# Fri3d_2024_Exp0_00.net
KiCad netlist of a schematic drawn in Altium Designer
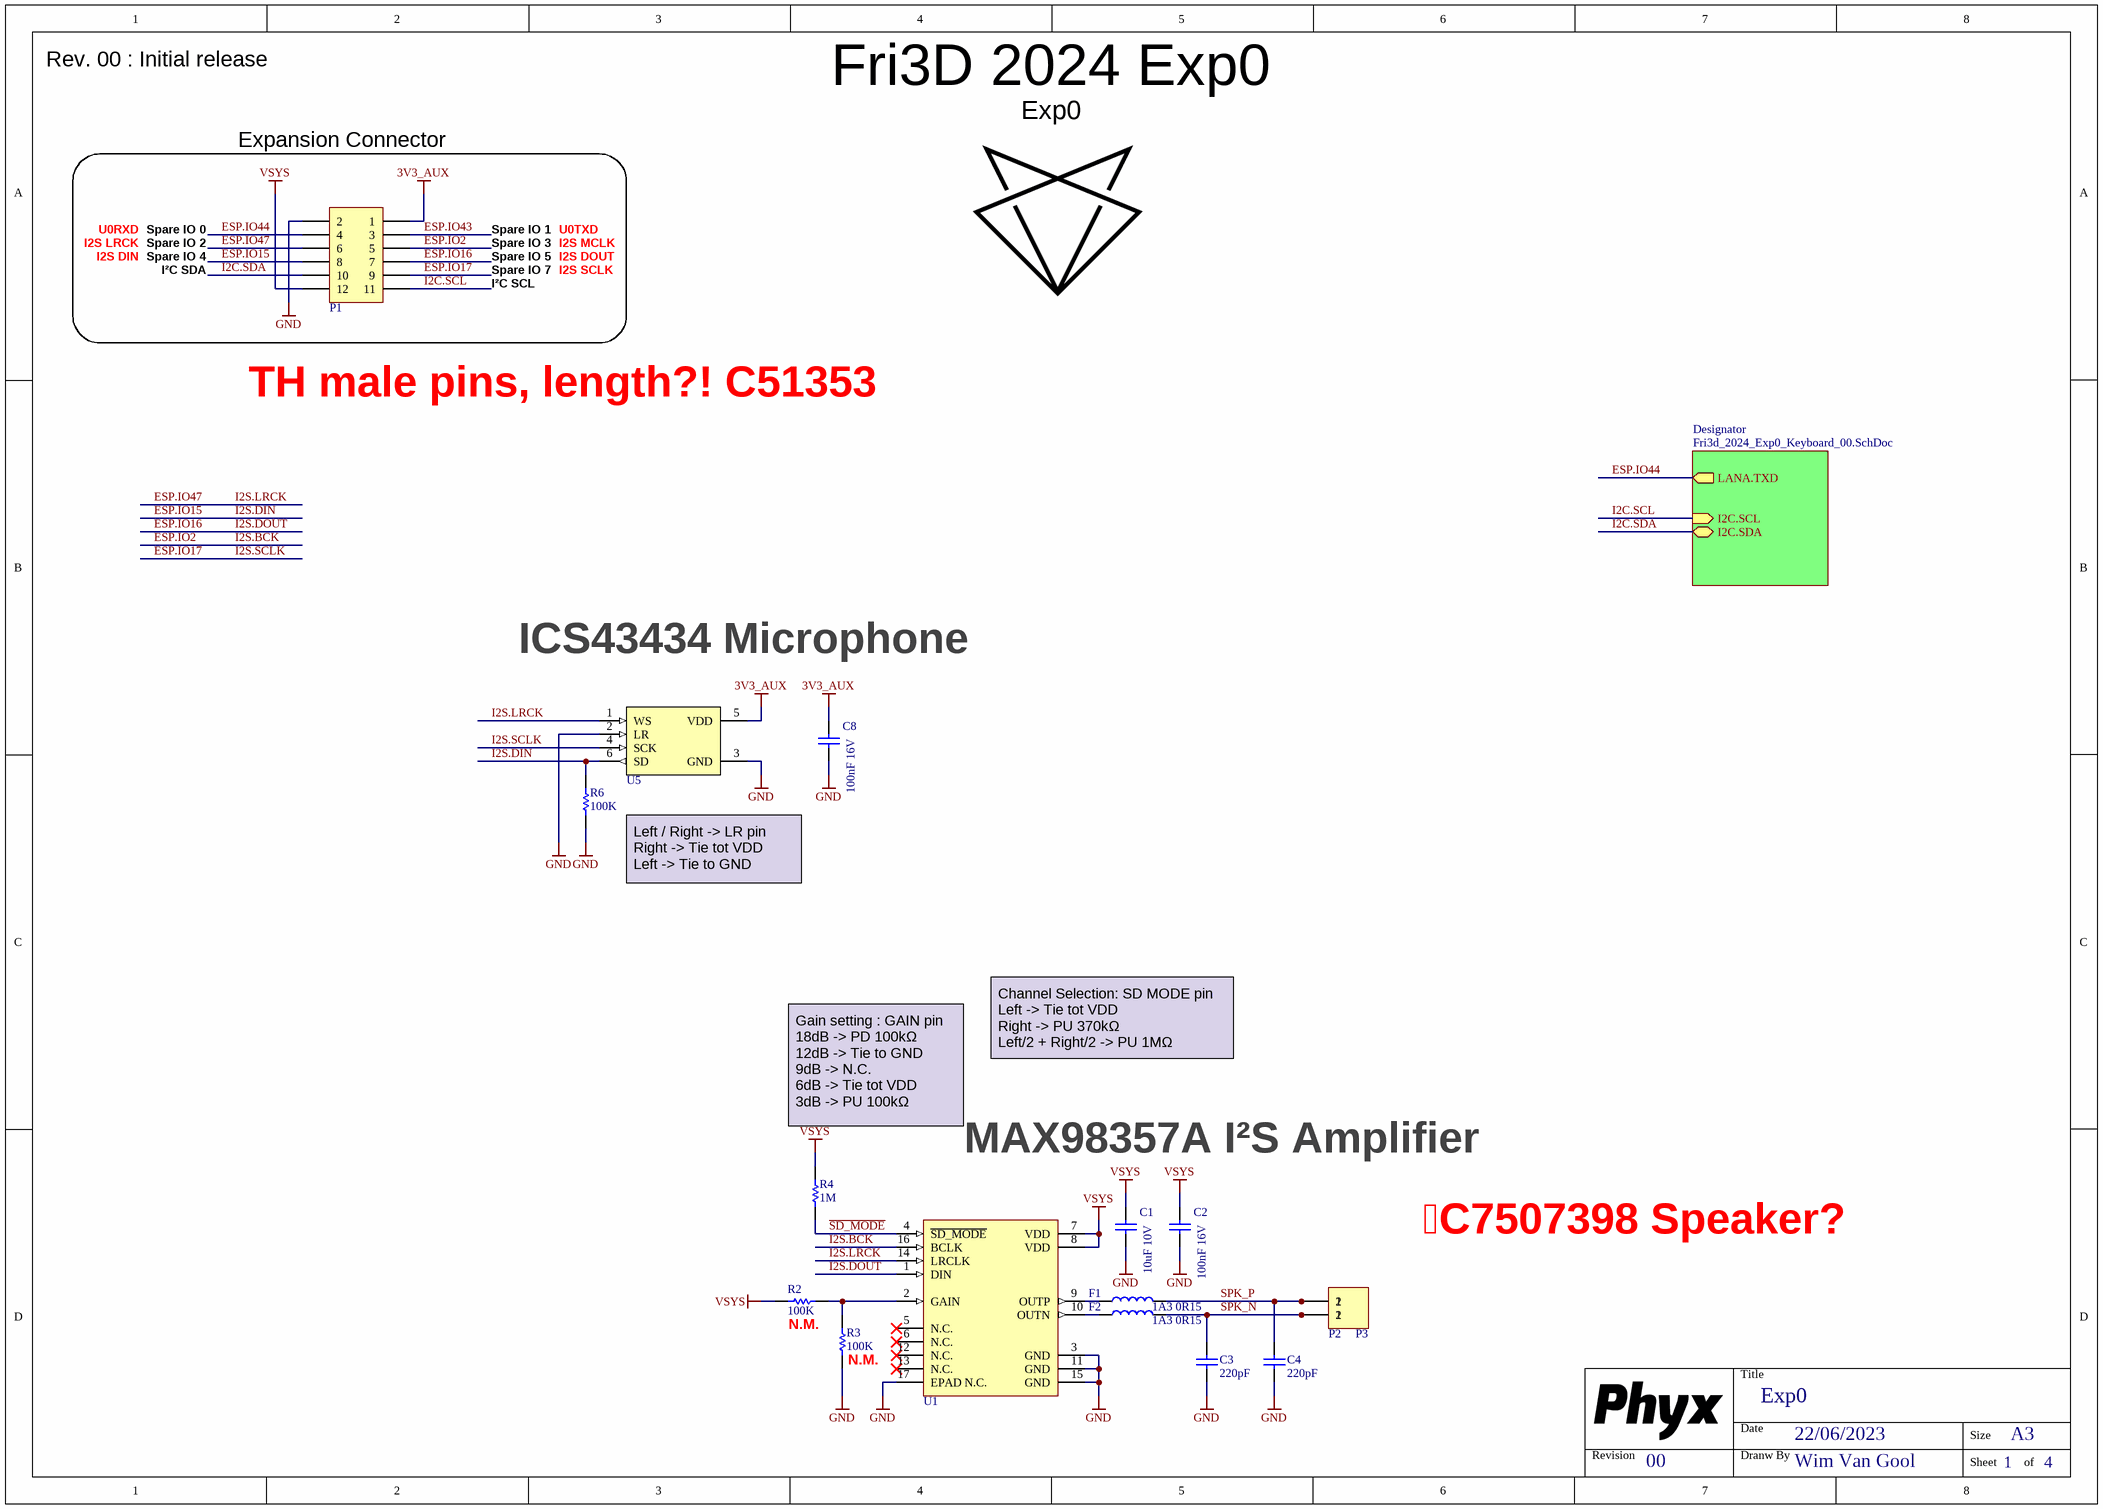
[diagram p0: Fri3d_2024_Exp0_00.SchDoc]

(export (version "E")
  (design (tool "Eeschema 10.0.6"))
  (components
    (comp (ref "C1")
      (value "10uF 10V")
      (footprint "C0805_N")
      (description "Capacitor Ceramic")
      (fields (field (name "Comment") "CAP_CERAMIC"))
      (libsource (lib "Phyx_Components") (part "CAP_CERAMIC"))
    )
    (comp (ref "C2")
      (value "100nF 16V")
      (footprint "C0603_N")
      (description "Capacitor Ceramic")
      (libsource (lib "Phyx_Components") (part "CAP_CERAMIC"))
    )
    (comp (ref "C3")
      (value "220pF")
      (footprint "C0603_N")
      (description "Capacitor Ceramic")
      (fields (field (name "Comment") "CAP_CERAMIC"))
      (libsource (lib "Phyx_Components") (part "CAP_CERAMIC"))
    )
    (comp (ref "C4")
      (value "220pF")
      (footprint "C0603_N")
      (description "Capacitor Ceramic")
      (fields (field (name "Comment") "CAP_CERAMIC"))
      (libsource (lib "Phyx_Components") (part "CAP_CERAMIC"))
    )
    (comp (ref "C8")
      (value "100nF 16V")
      (footprint "C0603_N")
      (description "Capacitor Ceramic")
      (libsource (lib "Phyx_Components") (part "CAP_CERAMIC"))
    )
    (comp (ref "F1")
      (value "1A3 0R15")
      (footprint "L0603")
      (fields (field (name "Comment") "BLM18KG601SN1D"))
      (libsource (lib "Phyx_Components") (part "FERRITE"))
    )
    (comp (ref "F2")
      (value "1A3 0R15")
      (footprint "L0603")
      (fields (field (name "Comment") "BLM18KG601SN1D"))
      (libsource (lib "Phyx_Components") (part "FERRITE"))
    )
    (comp (ref "P1")
      (value "Header 6X2")
      (footprint "HDR2X6")
      (libsource (lib "Phyx_Components") (part "Header 6X2"))
    )
    (comp (ref "P2")
      (value "Header 2.0mm Shrouded 2")
      (footprint "WE_620102131822")
      (libsource (lib "") (part "Header 2_1"))
    )
    (comp (ref "P3")
      (value "Header 2 RA")
      (footprint "HDR1X2_RA")
      (libsource (lib "Phyx_Components") (part "Header 2"))
    )
    (comp (ref "R2")
      (value "100K")
      (footprint "R0603_N")
      (fields (field (name "Comment") "RESISTOR"))
      (libsource (lib "Phyx_Components") (part "RESISTOR"))
    )
    (comp (ref "R3")
      (value "100K")
      (footprint "R0603_N")
      (fields (field (name "Comment") "RESISTOR"))
      (libsource (lib "Phyx_Components") (part "RESISTOR"))
    )
    (comp (ref "R4")
      (value "1M")
      (footprint "R0603_N")
      (fields (field (name "Comment") "RESISTOR"))
      (libsource (lib "Phyx_Components") (part "RESISTOR"))
    )
    (comp (ref "R6")
      (value "100K")
      (footprint "R0603_N")
      (fields (field (name "Comment") "RESISTOR"))
      (libsource (lib "Phyx_Components") (part "RESISTOR"))
    )
    (comp (ref "U1")
      (value "Mono I²S DAC AMP 3W 2.5~5.5V")
      (footprint "QFN_16_0.5_3X3")
      (description "=Description")
      (libsource (lib "Phyx_Components") (part "ADI_MAX98357_QFN"))
    )
    (comp (ref "U5")
      (value "I2S MIC ICS-43434")
      (footprint "TDK_ICS-43434")
      (description "=Description")
      (libsource (lib "Phyx_Components") (part "TDK_ICS-43434"))
    )
  )
  (nets
    (net (code "2") (name "/ESP.IO2") (class "Default")
      (node (ref "P1") (pin "5") (pinfunction "5_5") (pintype "passive"))
      (node (ref "U1") (pin "16") (pinfunction "BCLK_16") (pintype "input"))
    )
    (net (code "3") (name "/ESP.IO15") (class "Default")
      (node (ref "P1") (pin "8") (pinfunction "8_8") (pintype "passive"))
      (node (ref "R6") (pin "1") (pinfunction "1_1") (pintype "passive"))
      (node (ref "U5") (pin "6") (pinfunction "SD_6") (pintype "output"))
    )
    (net (code "4") (name "/ESP.IO16") (class "Default")
      (node (ref "P1") (pin "7") (pinfunction "7_7") (pintype "passive"))
      (node (ref "U1") (pin "1") (pinfunction "DIN_1") (pintype "input"))
    )
    (net (code "5") (name "/ESP.IO17") (class "Default")
      (node (ref "P1") (pin "9") (pinfunction "9_9") (pintype "passive"))
      (node (ref "U5") (pin "4") (pinfunction "SCK_4") (pintype "input"))
    )
    (net (code "6") (name "/ESP.IO43") (class "Default")
      (node (ref "P1") (pin "3") (pinfunction "3_3") (pintype "passive"))
    )
    (net (code "7") (name "/ESP.IO44") (class "Default")
      (node (ref "P1") (pin "4") (pinfunction "4_4") (pintype "passive"))
    )
    (net (code "8") (name "/ESP.IO47") (class "Default")
      (node (ref "P1") (pin "6") (pinfunction "6_6") (pintype "passive"))
      (node (ref "U1") (pin "14") (pinfunction "LRCLK_14") (pintype "input"))
      (node (ref "U5") (pin "1") (pinfunction "WS_1") (pintype "input"))
    )
    (net (code "9") (name "/I2C.SCL") (class "Default")
      (node (ref "P1") (pin "11") (pinfunction "11_11") (pintype "passive"))
    )
    (net (code "10") (name "/I2C.SDA") (class "Default")
      (node (ref "P1") (pin "10") (pinfunction "10_10") (pintype "passive"))
    )
    (net (code "11") (name "/SPK_N") (class "Default")
      (node (ref "C3") (pin "1") (pinfunction "1_1") (pintype "passive"))
      (node (ref "F2") (pin "2") (pinfunction "2_2") (pintype "passive"))
      (node (ref "P2") (pin "2") (pinfunction "2_2") (pintype "passive"))
      (node (ref "P3") (pin "1") (pinfunction "1_1") (pintype "passive"))
    )
    (net (code "12") (name "/SPK_P") (class "Default")
      (node (ref "C4") (pin "1") (pinfunction "1_1") (pintype "passive"))
      (node (ref "F1") (pin "2") (pinfunction "2_2") (pintype "passive"))
      (node (ref "P2") (pin "1") (pinfunction "1_1") (pintype "passive"))
      (node (ref "P3") (pin "2") (pinfunction "2_2") (pintype "passive"))
    )
    (net (code "13") (name "/~{SD_MODE}") (class "Default")
      (node (ref "R4") (pin "2") (pinfunction "2_2") (pintype "passive"))
      (node (ref "U1") (pin "4") (pinfunction "~{SD_MODE}_4") (pintype "input"))
    )
    (net (code "14") (name "3V3_AUX") (class "Default")
      (node (ref "C8") (pin "1") (pinfunction "1_1") (pintype "passive"))
      (node (ref "P1") (pin "1") (pinfunction "1_1") (pintype "passive"))
      (node (ref "U5") (pin "5") (pinfunction "VDD_5") (pintype "power_in"))
    )
    (net (code "15") (name "GND") (class "Default")
      (node (ref "C1") (pin "2") (pinfunction "2_2") (pintype "passive"))
      (node (ref "C2") (pin "2") (pinfunction "2_2") (pintype "passive"))
      (node (ref "C3") (pin "2") (pinfunction "2_2") (pintype "passive"))
      (node (ref "C4") (pin "2") (pinfunction "2_2") (pintype "passive"))
      (node (ref "C8") (pin "2") (pinfunction "2_2") (pintype "passive"))
      (node (ref "P1") (pin "2") (pinfunction "2_2") (pintype "passive"))
      (node (ref "R3") (pin "2") (pinfunction "2_2") (pintype "passive"))
      (node (ref "R6") (pin "2") (pinfunction "2_2") (pintype "passive"))
      (node (ref "U1") (pin "11") (pinfunction "GND_11") (pintype "power_in"))
      (node (ref "U1") (pin "15") (pinfunction "GND_15") (pintype "power_in"))
      (node (ref "U1") (pin "17") (pinfunction "EPAD_N.C._17") (pintype "passive"))
      (node (ref "U1") (pin "3") (pinfunction "GND_3") (pintype "power_in"))
      (node (ref "U5") (pin "2") (pinfunction "LR_2") (pintype "input"))
      (node (ref "U5") (pin "3") (pinfunction "GND_3") (pintype "passive"))
    )
    (net (code "16") (name "Net-(U1-GAIN)") (class "Default")
      (node (ref "R2") (pin "1") (pinfunction "1_1") (pintype "passive"))
      (node (ref "R3") (pin "1") (pinfunction "1_1") (pintype "passive"))
      (node (ref "U1") (pin "2") (pinfunction "GAIN_2") (pintype "input"))
    )
    (net (code "17") (name "Net-(U1-OUTN)") (class "Default")
      (node (ref "F2") (pin "1") (pinfunction "1_1") (pintype "passive"))
      (node (ref "U1") (pin "10") (pinfunction "OUTN_10") (pintype "output"))
    )
    (net (code "18") (name "Net-(U1-OUTP)") (class "Default")
      (node (ref "F1") (pin "1") (pinfunction "1_1") (pintype "passive"))
      (node (ref "U1") (pin "9") (pinfunction "OUTP_9") (pintype "output"))
    )
    (net (code "19") (name "VSYS") (class "Default")
      (node (ref "C1") (pin "1") (pinfunction "1_1") (pintype "passive"))
      (node (ref "C2") (pin "1") (pinfunction "1_1") (pintype "passive"))
      (node (ref "P1") (pin "12") (pinfunction "12_12") (pintype "passive"))
      (node (ref "R2") (pin "2") (pinfunction "2_2") (pintype "passive"))
      (node (ref "R4") (pin "1") (pinfunction "1_1") (pintype "passive"))
      (node (ref "U1") (pin "7") (pinfunction "VDD_7") (pintype "power_in"))
      (node (ref "U1") (pin "8") (pinfunction "VDD_8") (pintype "power_in"))
    )
    (net (code "20") (name "unconnected-(U1-N.C.-Pad5)") (class "Default")
      (node (ref "U1") (pin "5") (pinfunction "N.C._5") (pintype "passive+no_connect"))
    )
    (net (code "21") (name "unconnected-(U1-N.C.-Pad6)") (class "Default")
      (node (ref "U1") (pin "6") (pinfunction "N.C._6") (pintype "passive+no_connect"))
    )
    (net (code "22") (name "unconnected-(U1-N.C.-Pad12)") (class "Default")
      (node (ref "U1") (pin "12") (pinfunction "N.C._12") (pintype "passive+no_connect"))
    )
    (net (code "23") (name "unconnected-(U1-N.C.-Pad13)") (class "Default")
      (node (ref "U1") (pin "13") (pinfunction "N.C._13") (pintype "passive+no_connect"))
    )
  )
)
